# Power_Supplies.net
KiCad netlist of a schematic drawn in Altium Designer
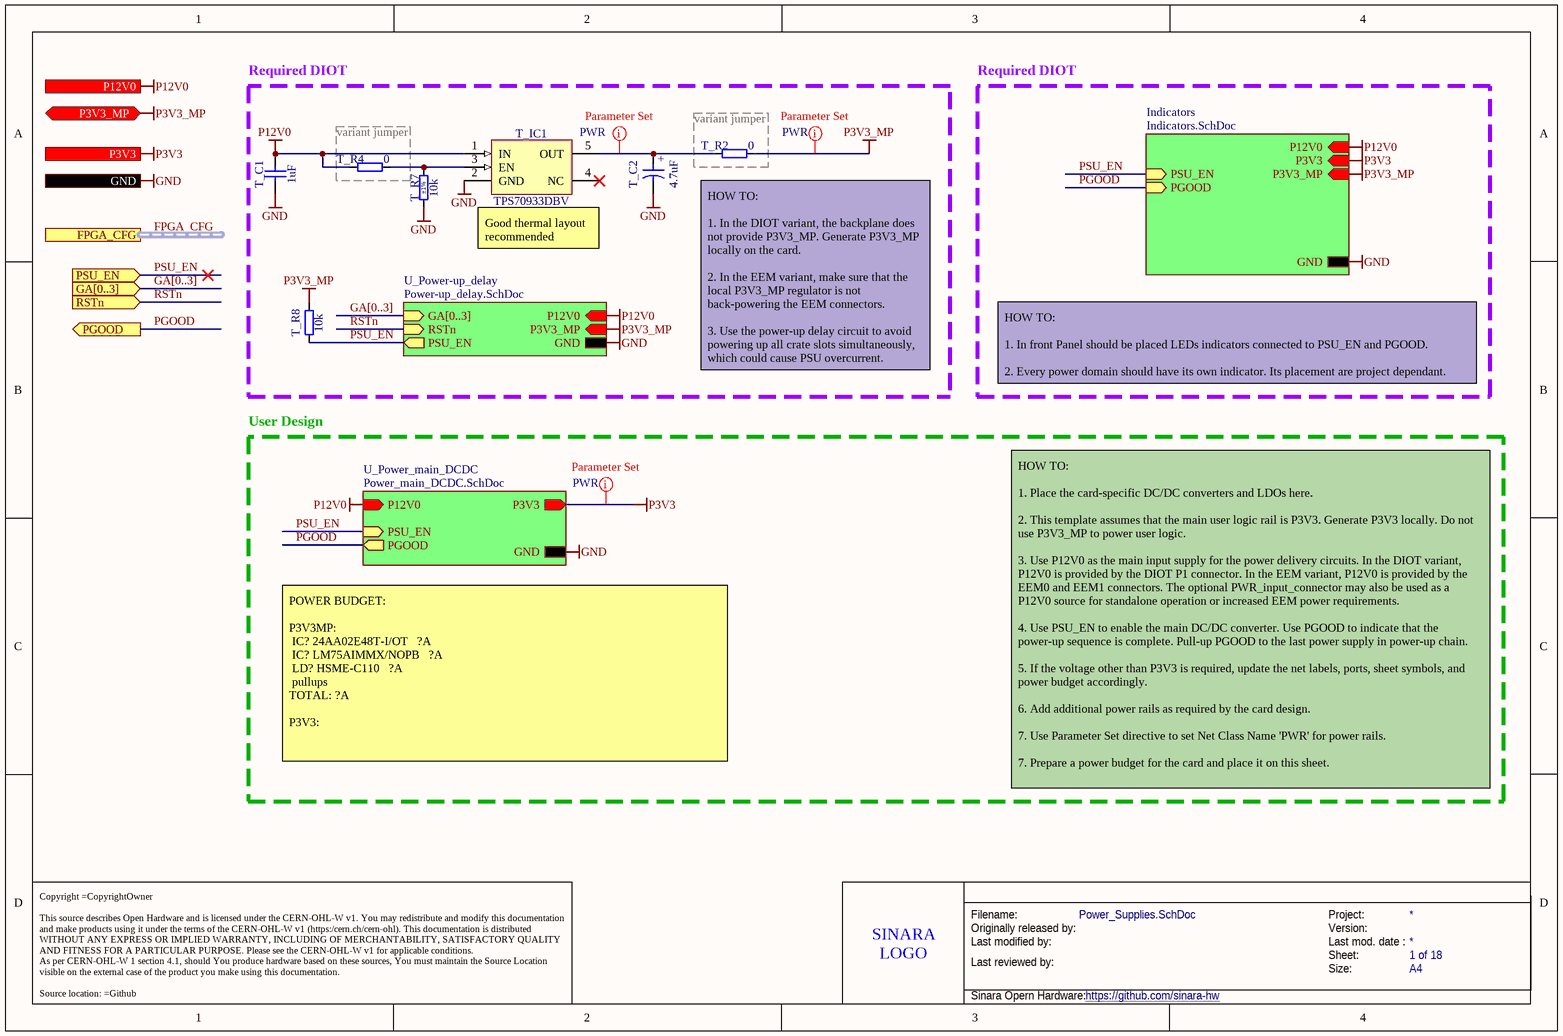
[diagram p0: Power_Supplies.SchDoc]

(export (version "E")
  (design (tool "Eeschema 10.0.6"))
  (components
    (comp (ref "T_C1")
      (value "1uF")
      (footprint "CAPC1608X87N")
      (description "Non-polarised capacitor")
      (fields
        (field (name "PART NUMBER") "CC0603_1UF_25V_10%_X7R")
        (field (name "VOLTAGE") "25V")
        (field (name "AUTHOR") "CERN DEM JLC")
      )
      (libsource (lib "Capacitors") (part "Capacitor - non polarized"))
    )
    (comp (ref "T_C2")
      (value "4.7uF")
      (footprint "CAPMP3216X180N")
      (description "Polarised capacitor")
      (fields
        (field (name "PART NUMBER") "CTE3216-18_4.7UF_10V_10%_AVX_TPSA475K010T1400")
        (field (name "VOLTAGE") "10V")
        (field (name "AUTHOR") "CERN DEM JLC")
      )
      (libsource (lib "Capacitors") (part "Capacitor - polarized"))
    )
    (comp (ref "T_IC1")
      (value "TPS70933DBV")
      (footprint "SOT95P280X145-5N")
      (description "150-mA, 30-V, 1-µA IQ Voltage Regulators with Enable")
      (fields (field (name "MANUFACTURER") "TEXAS INSTRUMENTS") (field (name "AUTHOR") "CERN DEM JLC"))
      (libsource (lib "ICs And Semiconductors") (part "TPS709"))
    )
    (comp (ref "T_R2")
      (value "0")
      (footprint "RESC1005X40N")
      (description "Resistor")
      (fields
        (field (name "PART NUMBER") "R0402_0R_JUMPER")
        (field (name "MANUFACTURER") "GENERIC")
        (field (name "AUTHOR") "CERN DEM JLC")
      )
      (libsource (lib "Resistors") (part "Resistor"))
    )
    (comp (ref "T_R4")
      (value "0")
      (footprint "RESC1005X40N")
      (description "Resistor")
      (fields
        (field (name "PART NUMBER") "R0402_0R_JUMPER")
        (field (name "MANUFACTURER") "GENERIC")
        (field (name "AUTHOR") "CERN DEM JLC")
      )
      (libsource (lib "Resistors") (part "Resistor"))
    )
    (comp (ref "T_R7")
      (value "10k")
      (footprint "RESC1005X40N")
      (description "Resistor - 1%")
      (fields
        (field (name "TOLERANCE") "±1%")
        (field (name "PART NUMBER") "R0402_10K_1%_0.0625W_100PPM")
        (field (name "POWER") "0.0625W")
        (field (name "AUTHOR") "CERN DEM JLC")
      )
      (libsource (lib "Resistors") (part "Resistor - 1%"))
    )
    (comp (ref "T_R8")
      (value "10k")
      (footprint "RESC1608X55N")
      (description "Resistor - 1%")
      (fields
        (field (name "PART NUMBER") "R0603_10K_1%_0.1W_100PPM")
        (field (name "POWER") "0.1W")
        (field (name "AUTHOR") "CERN DEM JLC")
      )
      (libsource (lib "Resistors") (part "Resistor - 1%"))
    )
  )
  (nets
    (net (code "8") (name "/PSU_EN") (class "Default")
      (node (ref "T_R8") (pin "1") (pinfunction "1_1") (pintype "passive"))
    )
    (net (code "11") (name "GND") (class "Default")
      (node (ref "T_C1") (pin "1") (pinfunction "1_1") (pintype "passive"))
      (node (ref "T_C2") (pin "2") (pinfunction "2_2") (pintype "passive"))
      (node (ref "T_IC1") (pin "2") (pinfunction "GND_2") (pintype "power_in"))
      (node (ref "T_R7") (pin "1") (pinfunction "1_1") (pintype "passive"))
    )
    (net (code "12") (name "Net-(T_IC1-EN)") (class "Default")
      (node (ref "T_IC1") (pin "3") (pinfunction "EN_3") (pintype "input"))
      (node (ref "T_R4") (pin "2") (pinfunction "2_2") (pintype "passive"))
      (node (ref "T_R7") (pin "2") (pinfunction "2_2") (pintype "passive"))
    )
    (net (code "13") (name "Net-(T_IC1-OUT)") (class "Default")
      (node (ref "T_C2") (pin "1") (pinfunction "1_1") (pintype "passive"))
      (node (ref "T_IC1") (pin "5") (pinfunction "OUT_5") (pintype "power_in"))
      (node (ref "T_R2") (pin "1") (pinfunction "1_1") (pintype "passive"))
    )
    (net (code "15") (name "P3V3_MP") (class "Default")
      (node (ref "T_R2") (pin "2") (pinfunction "2_2") (pintype "passive"))
      (node (ref "T_R8") (pin "2") (pinfunction "2_2") (pintype "passive"))
    )
    (net (code "16") (name "P12V0") (class "Default")
      (node (ref "T_C1") (pin "2") (pinfunction "2_2") (pintype "passive"))
      (node (ref "T_IC1") (pin "1") (pinfunction "IN_1") (pintype "input"))
      (node (ref "T_R4") (pin "1") (pinfunction "1_1") (pintype "passive"))
    )
    (net (code "17") (name "unconnected-(T_IC1-NC-Pad4)") (class "Default")
      (node (ref "T_IC1") (pin "4") (pinfunction "NC_4") (pintype "passive+no_connect"))
    )
  )
)
